# ReturnSlice.net
KiCad netlist of a schematic drawn in EAGLE
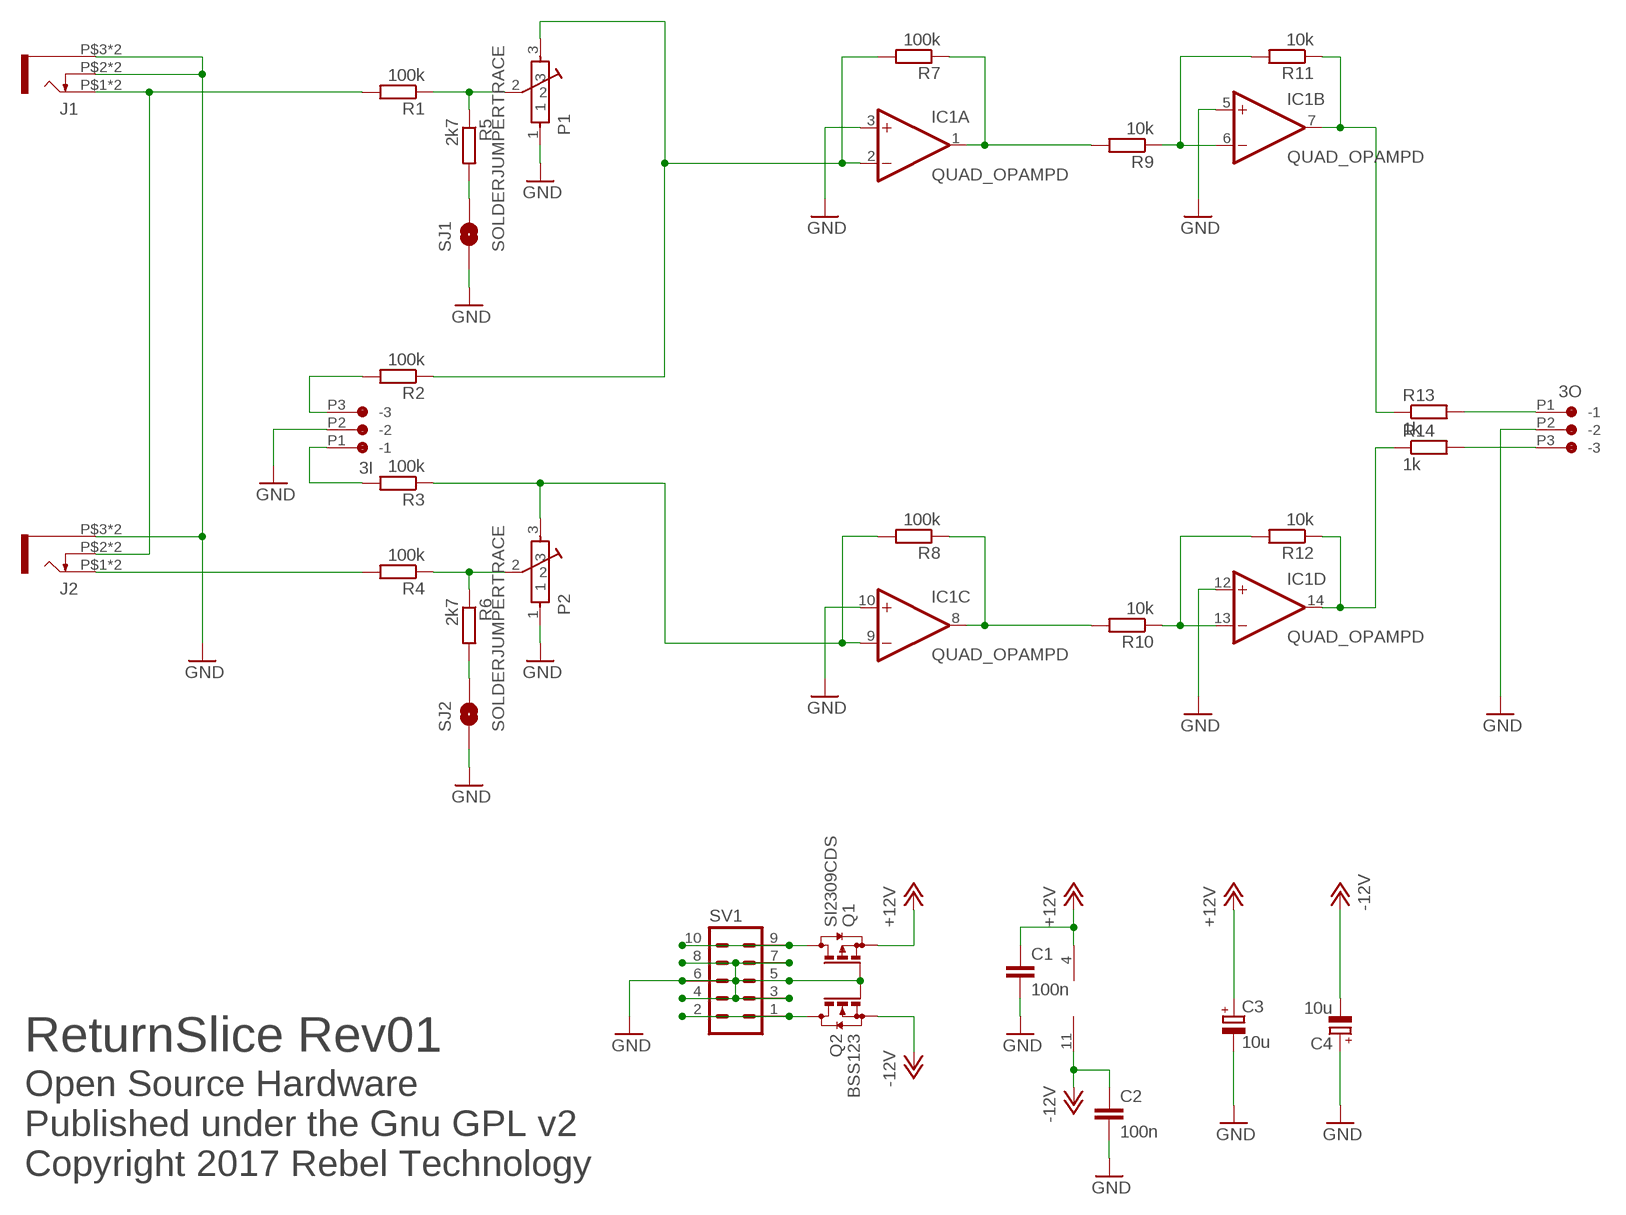
[diagram p0: schematic, sheet 1]

(export (version "E")
  (design (tool "Eeschema 10.0.6"))
  (components
    (comp (ref "3I")
      (value "CON-JST_PH_3W")
      (footprint "eagle-import:CON-JST_PH_3W")
      (libsource (lib "eagle-import") (part "CON-JST_PH_3W"))
    )
    (comp (ref "3O")
      (value "CON-JST_PH_3W")
      (footprint "eagle-import:CON-JST_PH_3W")
      (libsource (lib "eagle-import") (part "CON-JST_PH_3W"))
    )
    (comp (ref "C1")
      (value "100n")
      (footprint "eagle-import:C0603")
      (libsource (lib "eagle-import") (part "C-EUC0603"))
    )
    (comp (ref "C2")
      (value "100n")
      (footprint "eagle-import:C0603")
      (libsource (lib "eagle-import") (part "C-EUC0603"))
    )
    (comp (ref "C3")
      (value "10u")
      (footprint "eagle-import:153CLV-0505")
      (libsource (lib "eagle-import") (part "CPOL-EU153CLV-0505"))
    )
    (comp (ref "C4")
      (value "10u")
      (footprint "eagle-import:153CLV-0505")
      (libsource (lib "eagle-import") (part "CPOL-EU153CLV-0505"))
    )
    (comp (ref "IC1")
      (value "QUAD_OPAMPD")
      (footprint "eagle-import:SO14")
      (libsource (lib "eagle-import") (part "QUAD_OPAMPD"))
    )
    (comp (ref "J1")
      (value "JACK-UJ-3502-RSLOT")
      (footprint "eagle-import:UJ-3502-R-SLOT")
      (libsource (lib "eagle-import") (part "JACK-UJ-3502-RSLOT"))
    )
    (comp (ref "J2")
      (value "JACK-UJ-3502-RSLOT")
      (footprint "eagle-import:UJ-3502-R-SLOT")
      (libsource (lib "eagle-import") (part "JACK-UJ-3502-RSLOT"))
    )
    (comp (ref "P1")
      (value "10k")
      (footprint "eagle-import:POT-BOURNS-PTD901")
      (libsource (lib "eagle-import") (part "POT-BOURNS-PTD901"))
    )
    (comp (ref "P2")
      (value "10k")
      (footprint "eagle-import:POT-BOURNS-PTD901")
      (libsource (lib "eagle-import") (part "POT-BOURNS-PTD901"))
    )
    (comp (ref "Q1")
      (value "SI2309CDS")
      (footprint "eagle-import:SOT23")
      (libsource (lib "eagle-import") (part "BSS84"))
    )
    (comp (ref "Q2")
      (value "BSS123")
      (footprint "eagle-import:SOT23")
      (libsource (lib "eagle-import") (part "BSS123"))
    )
    (comp (ref "R1")
      (value "100k")
      (footprint "eagle-import:0603")
      (libsource (lib "eagle-import") (part "R-EU_0603"))
    )
    (comp (ref "R2")
      (value "100k")
      (footprint "eagle-import:0603")
      (libsource (lib "eagle-import") (part "R-EU_0603"))
    )
    (comp (ref "R3")
      (value "100k")
      (footprint "eagle-import:0603")
      (libsource (lib "eagle-import") (part "R-EU_0603"))
    )
    (comp (ref "R4")
      (value "100k")
      (footprint "eagle-import:0603")
      (libsource (lib "eagle-import") (part "R-EU_0603"))
    )
    (comp (ref "R5")
      (value "2k7")
      (footprint "eagle-import:0603")
      (libsource (lib "eagle-import") (part "R-EU_0603"))
    )
    (comp (ref "R6")
      (value "2k7")
      (footprint "eagle-import:0603")
      (libsource (lib "eagle-import") (part "R-EU_0603"))
    )
    (comp (ref "R7")
      (value "100k")
      (footprint "eagle-import:0603")
      (libsource (lib "eagle-import") (part "R-EU_0603"))
    )
    (comp (ref "R8")
      (value "100k")
      (footprint "eagle-import:0603")
      (libsource (lib "eagle-import") (part "R-EU_0603"))
    )
    (comp (ref "R9")
      (value "10k")
      (footprint "eagle-import:0603")
      (libsource (lib "eagle-import") (part "R-EU_0603"))
    )
    (comp (ref "R10")
      (value "10k")
      (footprint "eagle-import:0603")
      (libsource (lib "eagle-import") (part "R-EU_0603"))
    )
    (comp (ref "R11")
      (value "10k")
      (footprint "eagle-import:0603")
      (libsource (lib "eagle-import") (part "R-EU_0603"))
    )
    (comp (ref "R12")
      (value "10k")
      (footprint "eagle-import:0603")
      (libsource (lib "eagle-import") (part "R-EU_0603"))
    )
    (comp (ref "R13")
      (value "1k")
      (footprint "eagle-import:0603")
      (libsource (lib "eagle-import") (part "R-EU_0603"))
    )
    (comp (ref "R14")
      (value "1k")
      (footprint "eagle-import:0603")
      (libsource (lib "eagle-import") (part "R-EU_0603"))
    )
    (comp (ref "SJ1")
      (value "SOLDERJUMPERTRACE")
      (footprint "eagle-import:SJ_2S-TRACE")
      (libsource (lib "eagle-import") (part "SOLDERJUMPERTRACE"))
    )
    (comp (ref "SJ2")
      (value "SOLDERJUMPERTRACE")
      (footprint "eagle-import:SJ_2S-TRACE")
      (libsource (lib "eagle-import") (part "SOLDERJUMPERTRACE"))
    )
    (comp (ref "SV1")
      (value "MA05-2")
      (footprint "eagle-import:MA05-2")
      (libsource (lib "eagle-import") (part "MA05-2"))
    )
  )
  (nets
    (net (code "1") (name "+12V") (class "Default")
      (node (ref "C1") (pin "1") (pinfunction "1_1") (pintype "passive"))
      (node (ref "C3") (pin "+") (pinfunction "+_+") (pintype "passive"))
      (node (ref "IC1") (pin "4") (pinfunction "V+_4") (pintype "power_in"))
      (node (ref "Q1") (pin "2") (pinfunction "S_2") (pintype "passive"))
    )
    (net (code "2") (name "-12V") (class "Default")
      (node (ref "C2") (pin "1") (pinfunction "1_1") (pintype "passive"))
      (node (ref "C4") (pin "-") (pinfunction "-_-") (pintype "passive"))
      (node (ref "IC1") (pin "11") (pinfunction "V-_11") (pintype "power_in"))
      (node (ref "Q2") (pin "2") (pinfunction "S_2") (pintype "passive"))
    )
    (net (code "3") (name "GND") (class "Default")
      (node (ref "3I") (pin "P2") (pinfunction "-2_P2") (pintype "bidirectional"))
      (node (ref "3O") (pin "P2") (pinfunction "-2_P2") (pintype "bidirectional"))
      (node (ref "C1") (pin "2") (pinfunction "2_2") (pintype "passive"))
      (node (ref "C2") (pin "2") (pinfunction "2_2") (pintype "passive"))
      (node (ref "C3") (pin "-") (pinfunction "-_-") (pintype "passive"))
      (node (ref "C4") (pin "+") (pinfunction "+_+") (pintype "passive"))
      (node (ref "IC1") (pin "10") (pinfunction "+IN_10") (pintype "input"))
      (node (ref "IC1") (pin "12") (pinfunction "+IN_12") (pintype "input"))
      (node (ref "IC1") (pin "3") (pinfunction "+IN_3") (pintype "input"))
      (node (ref "IC1") (pin "5") (pinfunction "+IN_5") (pintype "input"))
      (node (ref "J1") (pin "P$2") (pinfunction "SW_P$2") (pintype "passive"))
      (node (ref "J1") (pin "P$2B") (pinfunction "SW_P$2B") (pintype "passive"))
      (node (ref "J1") (pin "P$3") (pinfunction "SLEEVE_P$3") (pintype "passive"))
      (node (ref "J1") (pin "P$3B") (pinfunction "SLEEVE_P$3B") (pintype "passive"))
      (node (ref "J2") (pin "P$3") (pinfunction "SLEEVE_P$3") (pintype "passive"))
      (node (ref "J2") (pin "P$3B") (pinfunction "SLEEVE_P$3B") (pintype "passive"))
      (node (ref "P1") (pin "1") (pinfunction "1_1") (pintype "bidirectional"))
      (node (ref "P2") (pin "1") (pinfunction "1_1") (pintype "bidirectional"))
      (node (ref "Q1") (pin "1") (pinfunction "G_1") (pintype "passive"))
      (node (ref "Q2") (pin "1") (pinfunction "G_1") (pintype "passive"))
      (node (ref "SJ1") (pin "1") (pinfunction "1_1") (pintype "passive"))
      (node (ref "SJ2") (pin "1") (pinfunction "1_1") (pintype "passive"))
      (node (ref "SV1") (pin "3") (pinfunction "3_3") (pintype "passive"))
      (node (ref "SV1") (pin "4") (pinfunction "4_4") (pintype "passive"))
      (node (ref "SV1") (pin "5") (pinfunction "5_5") (pintype "passive"))
      (node (ref "SV1") (pin "6") (pinfunction "6_6") (pintype "passive"))
      (node (ref "SV1") (pin "7") (pinfunction "7_7") (pintype "passive"))
      (node (ref "SV1") (pin "8") (pinfunction "8_8") (pintype "passive"))
    )
    (net (code "4") (name "Net-(3I--1)") (class "Default")
      (node (ref "3I") (pin "P1") (pinfunction "-1_P1") (pintype "bidirectional"))
      (node (ref "R3") (pin "2") (pinfunction "2_2") (pintype "passive"))
    )
    (net (code "5") (name "Net-(3I--3)") (class "Default")
      (node (ref "3I") (pin "P3") (pinfunction "-3_P3") (pintype "bidirectional"))
      (node (ref "R2") (pin "2") (pinfunction "2_2") (pintype "passive"))
    )
    (net (code "6") (name "Net-(3O--1)") (class "Default")
      (node (ref "3O") (pin "P1") (pinfunction "-1_P1") (pintype "bidirectional"))
      (node (ref "R13") (pin "2") (pinfunction "2_2") (pintype "passive"))
    )
    (net (code "7") (name "Net-(3O--3)") (class "Default")
      (node (ref "3O") (pin "P3") (pinfunction "-3_P3") (pintype "bidirectional"))
      (node (ref "R14") (pin "2") (pinfunction "2_2") (pintype "passive"))
    )
    (net (code "8") (name "Net-(IC1A--IN)") (class "Default")
      (node (ref "IC1") (pin "2") (pinfunction "-IN_2") (pintype "input"))
      (node (ref "P1") (pin "3") (pinfunction "3_3") (pintype "bidirectional"))
      (node (ref "R2") (pin "1") (pinfunction "1_1") (pintype "passive"))
      (node (ref "R7") (pin "2") (pinfunction "2_2") (pintype "passive"))
    )
    (net (code "9") (name "Net-(IC1A-OUT)") (class "Default")
      (node (ref "IC1") (pin "1") (pinfunction "OUT_1") (pintype "output"))
      (node (ref "R7") (pin "1") (pinfunction "1_1") (pintype "passive"))
      (node (ref "R9") (pin "2") (pinfunction "2_2") (pintype "passive"))
    )
    (net (code "10") (name "Net-(IC1B--IN)") (class "Default")
      (node (ref "IC1") (pin "6") (pinfunction "-IN_6") (pintype "input"))
      (node (ref "R11") (pin "2") (pinfunction "2_2") (pintype "passive"))
      (node (ref "R9") (pin "1") (pinfunction "1_1") (pintype "passive"))
    )
    (net (code "11") (name "Net-(IC1B-OUT)") (class "Default")
      (node (ref "IC1") (pin "7") (pinfunction "OUT_7") (pintype "output"))
      (node (ref "R11") (pin "1") (pinfunction "1_1") (pintype "passive"))
      (node (ref "R13") (pin "1") (pinfunction "1_1") (pintype "passive"))
    )
    (net (code "12") (name "Net-(IC1C--IN)") (class "Default")
      (node (ref "IC1") (pin "9") (pinfunction "-IN_9") (pintype "input"))
      (node (ref "P2") (pin "3") (pinfunction "3_3") (pintype "bidirectional"))
      (node (ref "R3") (pin "1") (pinfunction "1_1") (pintype "passive"))
      (node (ref "R8") (pin "2") (pinfunction "2_2") (pintype "passive"))
    )
    (net (code "13") (name "Net-(IC1C-OUT)") (class "Default")
      (node (ref "IC1") (pin "8") (pinfunction "OUT_8") (pintype "output"))
      (node (ref "R10") (pin "2") (pinfunction "2_2") (pintype "passive"))
      (node (ref "R8") (pin "1") (pinfunction "1_1") (pintype "passive"))
    )
    (net (code "14") (name "Net-(IC1D--IN)") (class "Default")
      (node (ref "IC1") (pin "13") (pinfunction "-IN_13") (pintype "input"))
      (node (ref "R10") (pin "1") (pinfunction "1_1") (pintype "passive"))
      (node (ref "R12") (pin "2") (pinfunction "2_2") (pintype "passive"))
    )
    (net (code "15") (name "Net-(IC1D-OUT)") (class "Default")
      (node (ref "IC1") (pin "14") (pinfunction "OUT_14") (pintype "output"))
      (node (ref "R12") (pin "1") (pinfunction "1_1") (pintype "passive"))
      (node (ref "R14") (pin "1") (pinfunction "1_1") (pintype "passive"))
    )
    (net (code "16") (name "Net-(J1-TIP-PadP$1)") (class "Default")
      (node (ref "J1") (pin "P$1") (pinfunction "TIP_P$1") (pintype "passive"))
      (node (ref "J1") (pin "P$1B") (pinfunction "TIP_P$1B") (pintype "passive"))
      (node (ref "J2") (pin "P$2") (pinfunction "SW_P$2") (pintype "passive"))
      (node (ref "J2") (pin "P$2B") (pinfunction "SW_P$2B") (pintype "passive"))
      (node (ref "R1") (pin "2") (pinfunction "2_2") (pintype "passive"))
    )
    (net (code "17") (name "Net-(J2-TIP-PadP$1)") (class "Default")
      (node (ref "J2") (pin "P$1") (pinfunction "TIP_P$1") (pintype "passive"))
      (node (ref "J2") (pin "P$1B") (pinfunction "TIP_P$1B") (pintype "passive"))
      (node (ref "R4") (pin "2") (pinfunction "2_2") (pintype "passive"))
    )
    (net (code "18") (name "Net-(P1-Pad2)") (class "Default")
      (node (ref "P1") (pin "2") (pinfunction "2_2") (pintype "bidirectional"))
      (node (ref "R1") (pin "1") (pinfunction "1_1") (pintype "passive"))
      (node (ref "R5") (pin "1") (pinfunction "1_1") (pintype "passive"))
    )
    (net (code "19") (name "Net-(P2-Pad2)") (class "Default")
      (node (ref "P2") (pin "2") (pinfunction "2_2") (pintype "bidirectional"))
      (node (ref "R4") (pin "1") (pinfunction "1_1") (pintype "passive"))
      (node (ref "R6") (pin "1") (pinfunction "1_1") (pintype "passive"))
    )
    (net (code "20") (name "Net-(Q1-D)") (class "Default")
      (node (ref "Q1") (pin "3") (pinfunction "D_3") (pintype "passive"))
      (node (ref "SV1") (pin "10") (pinfunction "10_10") (pintype "passive"))
      (node (ref "SV1") (pin "9") (pinfunction "9_9") (pintype "passive"))
    )
    (net (code "21") (name "Net-(Q2-D)") (class "Default")
      (node (ref "Q2") (pin "3") (pinfunction "D_3") (pintype "passive"))
      (node (ref "SV1") (pin "1") (pinfunction "1_1") (pintype "passive"))
      (node (ref "SV1") (pin "2") (pinfunction "2_2") (pintype "passive"))
    )
    (net (code "22") (name "Net-(R5-Pad2)") (class "Default")
      (node (ref "R5") (pin "2") (pinfunction "2_2") (pintype "passive"))
      (node (ref "SJ1") (pin "2") (pinfunction "2_2") (pintype "passive"))
    )
    (net (code "23") (name "Net-(R6-Pad2)") (class "Default")
      (node (ref "R6") (pin "2") (pinfunction "2_2") (pintype "passive"))
      (node (ref "SJ2") (pin "2") (pinfunction "2_2") (pintype "passive"))
    )
  )
)
